# POWER_SUPPLY.net
KiCad netlist of a schematic drawn in Altium Designer
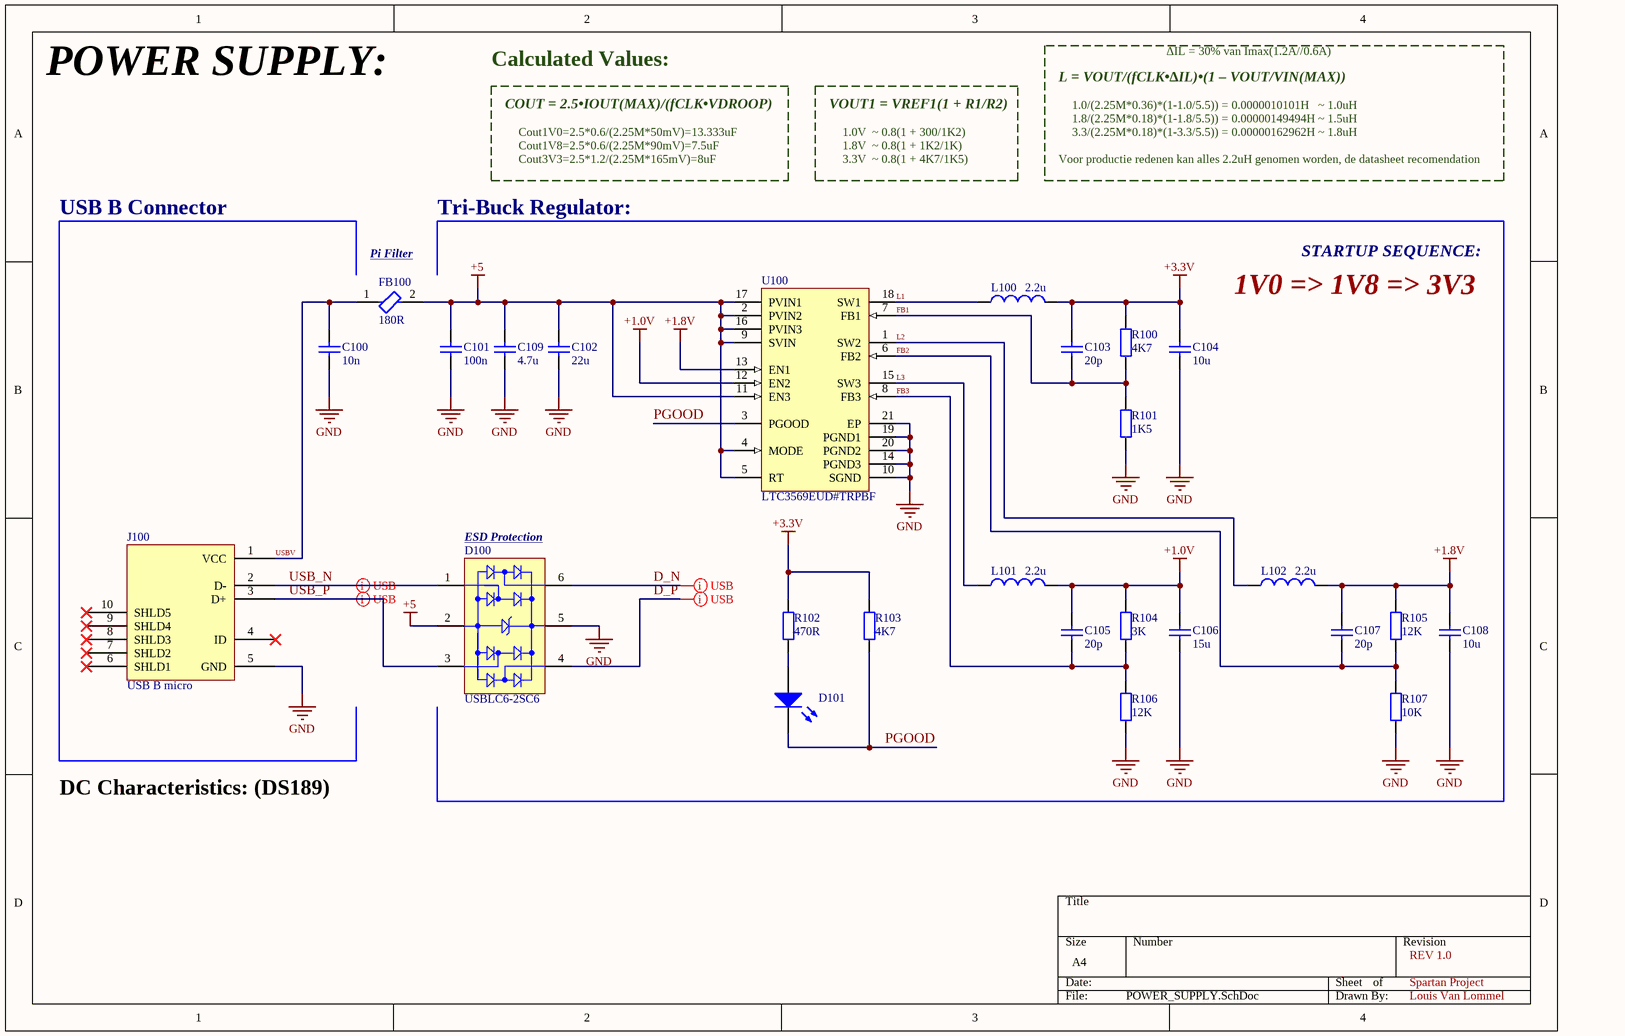
[diagram p0: POWER_SUPPLY.SchDoc]

(export (version "E")
  (design (tool "Eeschema 10.0.6"))
  (components
    (comp (ref "C100")
      (value "10n")
      (footprint "CAP_0603")
      (description "Capacitor")
      (fields (field (name "PUBLISHER") "Altium Limited"))
      (libsource (lib "Miscellaneous Devices") (part "Cap"))
    )
    (comp (ref "C101")
      (value "100n")
      (footprint "CAP_0603")
      (description "Capacitor")
      (fields (field (name "PUBLISHER") "Altium Limited"))
      (libsource (lib "Miscellaneous Devices") (part "Cap"))
    )
    (comp (ref "C102")
      (value "22u")
      (footprint "CAP_1210")
      (description "Capacitor")
      (fields (field (name "PUBLISHER") "Altium Limited"))
      (libsource (lib "Miscellaneous Devices") (part "Cap"))
    )
    (comp (ref "C103")
      (value "20p")
      (footprint "CAP_0603")
      (description "Capacitor")
      (fields (field (name "Comment") "20pF") (field (name "PUBLISHER") "Altium Limited"))
      (libsource (lib "Miscellaneous Devices") (part "Cap"))
    )
    (comp (ref "C104")
      (value "10u")
      (footprint "CAP_1210")
      (description "Capacitor")
      (fields (field (name "Comment") "10uF") (field (name "PUBLISHER") "Altium Limited"))
      (libsource (lib "Miscellaneous Devices") (part "Cap"))
    )
    (comp (ref "C105")
      (value "20p")
      (footprint "CAP_0603")
      (description "Capacitor")
      (fields (field (name "Comment") "20pF") (field (name "PUBLISHER") "Altium Limited"))
      (libsource (lib "Miscellaneous Devices") (part "Cap"))
    )
    (comp (ref "C106")
      (value "15u")
      (footprint "CAP_1210")
      (description "Capacitor")
      (fields (field (name "Comment") "15uF") (field (name "PUBLISHER") "Altium Limited"))
      (libsource (lib "Miscellaneous Devices") (part "Cap"))
    )
    (comp (ref "C107")
      (value "20p")
      (footprint "CAP_0603")
      (description "Capacitor")
      (fields (field (name "Comment") "20pF") (field (name "PUBLISHER") "Altium Limited"))
      (libsource (lib "Miscellaneous Devices") (part "Cap"))
    )
    (comp (ref "C108")
      (value "10u")
      (footprint "CAP_1210")
      (description "Capacitor")
      (fields (field (name "Comment") "10uF") (field (name "PUBLISHER") "Altium Limited"))
      (libsource (lib "Miscellaneous Devices") (part "Cap"))
    )
    (comp (ref "C109")
      (value "4.7u")
      (footprint "CAP_0603")
      (description "Capacitor")
      (fields (field (name "PUBLISHER") "Altium Limited"))
      (libsource (lib "Miscellaneous Devices") (part "Cap"))
    )
    (comp (ref "D100")
      (value "USBLC6-2SC6")
      (footprint "STM-SOT23-6L_V")
      (description "Very low capacitance ESD protection, 3.5 pF, -40 to 125 degC, 6-Pin SOT23, RoHS, Tape and Reel")
      (fields (field (name "MANUFACTURER") "STMicroelectronics"))
      (libsource (lib "Altium Content Vault") (part "STM-USB_DVI_HDMIULC6-4SC6X-SOT23-6L"))
    )
    (comp (ref "D101")
      (value "LED")
      (footprint "LED_0603")
      (description "Typical INFRARED GaAs LED")
      (fields (field (name "PUBLISHER") "Altium Limited"))
      (libsource (lib "Miscellaneous Devices") (part "LED0"))
    )
    (comp (ref "FB100")
      (value "180R")
      (footprint "CAP_0805")
      (description "Chip Ferrite Bead, 0402, 1000Ω @ 100MHz, 0.65Ω, 25%, 300mA")
      (fields (field (name "TOLERANCE") "25%"))
      (libsource (lib "Schematic_Symbols") (part "Ferrite Bead"))
    )
    (comp (ref "J100")
      (value "USB B micro")
      (footprint "USB Micro B")
      (libsource (lib "Schematic_Symbols") (part "USB micro B"))
    )
    (comp (ref "L100")
      (value "2.2u")
      (footprint "IND4x4mm")
      (description "Inductor")
      (fields (field (name "Comment") "2.2uH") (field (name "PUBLISHER") "Altium Limited"))
      (libsource (lib "Miscellaneous Devices") (part "Inductor"))
    )
    (comp (ref "L101")
      (value "2.2u")
      (footprint "IND4x4mm")
      (description "Inductor")
      (fields (field (name "Comment") "2.2uH") (field (name "PUBLISHER") "Altium Limited"))
      (libsource (lib "Miscellaneous Devices") (part "Inductor"))
    )
    (comp (ref "L102")
      (value "2.2u")
      (footprint "IND4x4mm")
      (description "Inductor")
      (fields (field (name "Comment") "2.2uH") (field (name "PUBLISHER") "Altium Limited"))
      (libsource (lib "Miscellaneous Devices") (part "Inductor"))
    )
    (comp (ref "R100")
      (value "4K7")
      (footprint "RES_0603")
      (description "Resistor")
      (fields (field (name "PUBLISHER") "Altium Limited"))
      (libsource (lib "Miscellaneous Devices") (part "Res2"))
    )
    (comp (ref "R101")
      (value "1K5")
      (footprint "RES_0603")
      (description "Resistor")
      (fields (field (name "PUBLISHER") "Altium Limited"))
      (libsource (lib "Miscellaneous Devices") (part "Res2"))
    )
    (comp (ref "R102")
      (value "470R")
      (footprint "RES_0603")
      (description "Resistor")
      (fields (field (name "Comment") "470") (field (name "PUBLISHER") "Altium Limited"))
      (libsource (lib "Miscellaneous Devices") (part "Res2"))
    )
    (comp (ref "R103")
      (value "4K7")
      (footprint "RES_0603")
      (description "DNP R103")
      (fields (field (name "PUBLISHER") "Altium Limited"))
      (libsource (lib "Miscellaneous Devices") (part "Res2"))
    )
    (comp (ref "R104")
      (value "3K")
      (footprint "RES_0603")
      (description "Resistor")
      (fields (field (name "PUBLISHER") "Altium Limited"))
      (libsource (lib "Miscellaneous Devices") (part "Res2"))
    )
    (comp (ref "R105")
      (value "12K")
      (footprint "RES_0603")
      (description "Resistor")
      (fields (field (name "PUBLISHER") "Altium Limited"))
      (libsource (lib "Miscellaneous Devices") (part "Res2"))
    )
    (comp (ref "R106")
      (value "12K")
      (footprint "RES_0603")
      (description "Resistor")
      (fields (field (name "PUBLISHER") "Altium Limited"))
      (libsource (lib "Miscellaneous Devices") (part "Res2"))
    )
    (comp (ref "R107")
      (value "10K")
      (footprint "RES_0603")
      (description "Resistor")
      (fields (field (name "PUBLISHER") "Altium Limited"))
      (libsource (lib "Miscellaneous Devices") (part "Res2"))
    )
    (comp (ref "U100")
      (value "LTC3569EUD#TRPBF")
      (footprint "LT-UD-20_N")
      (fields (field (name "MANUFACTURER") "Linear Technology"))
      (libsource (lib "Altium Content Vault") (part "LT-LTC3569-UD-20"))
    )
  )
  (nets
    (net (code "1") (name "+1.0V") (class "Default")
      (node (ref "C105") (pin "2") (pinfunction "2_2") (pintype "passive"))
      (node (ref "C106") (pin "2") (pinfunction "2_2") (pintype "passive"))
      (node (ref "L101") (pin "2") (pinfunction "2_2") (pintype "passive"))
      (node (ref "R104") (pin "2") (pinfunction "2_2") (pintype "passive"))
      (node (ref "U100") (pin "12") (pinfunction "EN2_12") (pintype "input"))
    )
    (net (code "2") (name "+1.8V") (class "Default")
      (node (ref "C107") (pin "2") (pinfunction "2_2") (pintype "passive"))
      (node (ref "C108") (pin "2") (pinfunction "2_2") (pintype "passive"))
      (node (ref "L102") (pin "2") (pinfunction "2_2") (pintype "passive"))
      (node (ref "R105") (pin "2") (pinfunction "2_2") (pintype "passive"))
      (node (ref "U100") (pin "13") (pinfunction "EN1_13") (pintype "input"))
    )
    (net (code "3") (name "+3.3V") (class "Default")
      (node (ref "C103") (pin "2") (pinfunction "2_2") (pintype "passive"))
      (node (ref "C104") (pin "2") (pinfunction "2_2") (pintype "passive"))
      (node (ref "L100") (pin "2") (pinfunction "2_2") (pintype "passive"))
      (node (ref "R100") (pin "2") (pinfunction "2_2") (pintype "passive"))
      (node (ref "R102") (pin "2") (pinfunction "2_2") (pintype "passive"))
      (node (ref "R103") (pin "2") (pinfunction "2_2") (pintype "passive"))
    )
    (net (code "4") (name "+5") (class "Default")
      (node (ref "C101") (pin "2") (pinfunction "2_2") (pintype "passive"))
      (node (ref "C102") (pin "2") (pinfunction "2_2") (pintype "passive"))
      (node (ref "C109") (pin "2") (pinfunction "2_2") (pintype "passive"))
      (node (ref "D100") (pin "2") (pinfunction "GND_2") (pintype "passive"))
      (node (ref "FB100") (pin "2") (pinfunction "2_2") (pintype "passive"))
      (node (ref "U100") (pin "11") (pinfunction "EN3_11") (pintype "input"))
      (node (ref "U100") (pin "16") (pinfunction "PVIN3_16") (pintype "power_in"))
      (node (ref "U100") (pin "17") (pinfunction "PVIN1_17") (pintype "power_in"))
      (node (ref "U100") (pin "2") (pinfunction "PVIN2_2") (pintype "power_in"))
      (node (ref "U100") (pin "4") (pinfunction "MODE_4") (pintype "input"))
      (node (ref "U100") (pin "5") (pinfunction "RT_5") (pintype "passive"))
      (node (ref "U100") (pin "9") (pinfunction "SVIN_9") (pintype "power_in"))
    )
    (net (code "5") (name "/D_N") (class "Default")
      (node (ref "D100") (pin "6") (pinfunction "I/O_4_6") (pintype "passive"))
    )
    (net (code "6") (name "/D_P") (class "Default")
      (node (ref "D100") (pin "4") (pinfunction "I/O_3_4") (pintype "passive"))
    )
    (net (code "7") (name "/FB1") (class "Default")
      (node (ref "C103") (pin "1") (pinfunction "1_1") (pintype "passive"))
      (node (ref "R100") (pin "1") (pinfunction "1_1") (pintype "passive"))
      (node (ref "R101") (pin "2") (pinfunction "2_2") (pintype "passive"))
      (node (ref "U100") (pin "7") (pinfunction "FB1_7") (pintype "input"))
    )
    (net (code "8") (name "/FB2") (class "Default")
      (node (ref "C107") (pin "1") (pinfunction "1_1") (pintype "passive"))
      (node (ref "R105") (pin "1") (pinfunction "1_1") (pintype "passive"))
      (node (ref "R107") (pin "2") (pinfunction "2_2") (pintype "passive"))
      (node (ref "U100") (pin "6") (pinfunction "FB2_6") (pintype "input"))
    )
    (net (code "9") (name "/FB3") (class "Default")
      (node (ref "C105") (pin "1") (pinfunction "1_1") (pintype "passive"))
      (node (ref "R104") (pin "1") (pinfunction "1_1") (pintype "passive"))
      (node (ref "R106") (pin "2") (pinfunction "2_2") (pintype "passive"))
      (node (ref "U100") (pin "8") (pinfunction "FB3_8") (pintype "input"))
    )
    (net (code "10") (name "/L1") (class "Default")
      (node (ref "L100") (pin "1") (pinfunction "1_1") (pintype "passive"))
      (node (ref "U100") (pin "18") (pinfunction "SW1_18") (pintype "power_in"))
    )
    (net (code "11") (name "/L2") (class "Default")
      (node (ref "L102") (pin "1") (pinfunction "1_1") (pintype "passive"))
      (node (ref "U100") (pin "1") (pinfunction "SW2_1") (pintype "power_in"))
    )
    (net (code "12") (name "/L3") (class "Default")
      (node (ref "L101") (pin "1") (pinfunction "1_1") (pintype "passive"))
      (node (ref "U100") (pin "15") (pinfunction "SW3_15") (pintype "power_in"))
    )
    (net (code "13") (name "/PGOOD") (class "Default")
      (node (ref "D101") (pin "2") (pinfunction "K_2") (pintype "passive"))
      (node (ref "R103") (pin "1") (pinfunction "1_1") (pintype "passive"))
      (node (ref "U100") (pin "3") (pinfunction "PGOOD_3") (pintype "open_collector"))
    )
    (net (code "14") (name "/USBV") (class "Default")
      (node (ref "C100") (pin "2") (pinfunction "2_2") (pintype "passive"))
      (node (ref "FB100") (pin "1") (pinfunction "1_1") (pintype "passive"))
      (node (ref "J100") (pin "1") (pinfunction "VCC_1") (pintype "passive"))
    )
    (net (code "15") (name "/USB_N") (class "Default")
      (node (ref "D100") (pin "1") (pinfunction "I/O_1_1") (pintype "passive"))
      (node (ref "J100") (pin "2") (pinfunction "D-_2") (pintype "passive"))
    )
    (net (code "16") (name "/USB_P") (class "Default")
      (node (ref "D100") (pin "3") (pinfunction "I/O_2_3") (pintype "passive"))
      (node (ref "J100") (pin "3") (pinfunction "D+_3") (pintype "passive"))
    )
    (net (code "17") (name "GND") (class "Default")
      (node (ref "C100") (pin "1") (pinfunction "1_1") (pintype "passive"))
      (node (ref "C101") (pin "1") (pinfunction "1_1") (pintype "passive"))
      (node (ref "C102") (pin "1") (pinfunction "1_1") (pintype "passive"))
      (node (ref "C104") (pin "1") (pinfunction "1_1") (pintype "passive"))
      (node (ref "C106") (pin "1") (pinfunction "1_1") (pintype "passive"))
      (node (ref "C108") (pin "1") (pinfunction "1_1") (pintype "passive"))
      (node (ref "C109") (pin "1") (pinfunction "1_1") (pintype "passive"))
      (node (ref "D100") (pin "5") (pinfunction "VBUS_5") (pintype "passive"))
      (node (ref "J100") (pin "5") (pinfunction "GND_5") (pintype "passive"))
      (node (ref "R101") (pin "1") (pinfunction "1_1") (pintype "passive"))
      (node (ref "R106") (pin "1") (pinfunction "1_1") (pintype "passive"))
      (node (ref "R107") (pin "1") (pinfunction "1_1") (pintype "passive"))
      (node (ref "U100") (pin "10") (pinfunction "SGND_10") (pintype "power_in"))
      (node (ref "U100") (pin "14") (pinfunction "PGND3_14") (pintype "power_in"))
      (node (ref "U100") (pin "19") (pinfunction "PGND1_19") (pintype "power_in"))
      (node (ref "U100") (pin "20") (pinfunction "PGND2_20") (pintype "power_in"))
      (node (ref "U100") (pin "21") (pinfunction "EP_21") (pintype "power_in"))
    )
    (net (code "18") (name "Net-(D101-A)") (class "Default")
      (node (ref "D101") (pin "1") (pinfunction "A_1") (pintype "passive"))
      (node (ref "R102") (pin "1") (pinfunction "1_1") (pintype "passive"))
    )
    (net (code "19") (name "unconnected-(J100-ID-Pad4)") (class "Default")
      (node (ref "J100") (pin "4") (pinfunction "ID_4") (pintype "passive+no_connect"))
    )
    (net (code "20") (name "unconnected-(J100-SHLD1-Pad6)") (class "Default")
      (node (ref "J100") (pin "6") (pinfunction "SHLD1_6") (pintype "passive+no_connect"))
    )
    (net (code "21") (name "unconnected-(J100-SHLD2-Pad7)") (class "Default")
      (node (ref "J100") (pin "7") (pinfunction "SHLD2_7") (pintype "passive+no_connect"))
    )
    (net (code "22") (name "unconnected-(J100-SHLD3-Pad8)") (class "Default")
      (node (ref "J100") (pin "8") (pinfunction "SHLD3_8") (pintype "passive+no_connect"))
    )
    (net (code "23") (name "unconnected-(J100-SHLD4-Pad9)") (class "Default")
      (node (ref "J100") (pin "9") (pinfunction "SHLD4_9") (pintype "passive+no_connect"))
    )
    (net (code "24") (name "unconnected-(J100-SHLD5-Pad10)") (class "Default")
      (node (ref "J100") (pin "10") (pinfunction "SHLD5_10") (pintype "passive+no_connect"))
    )
  )
)
